# displaycontrol.net
KiCad netlist of a schematic drawn in EAGLE
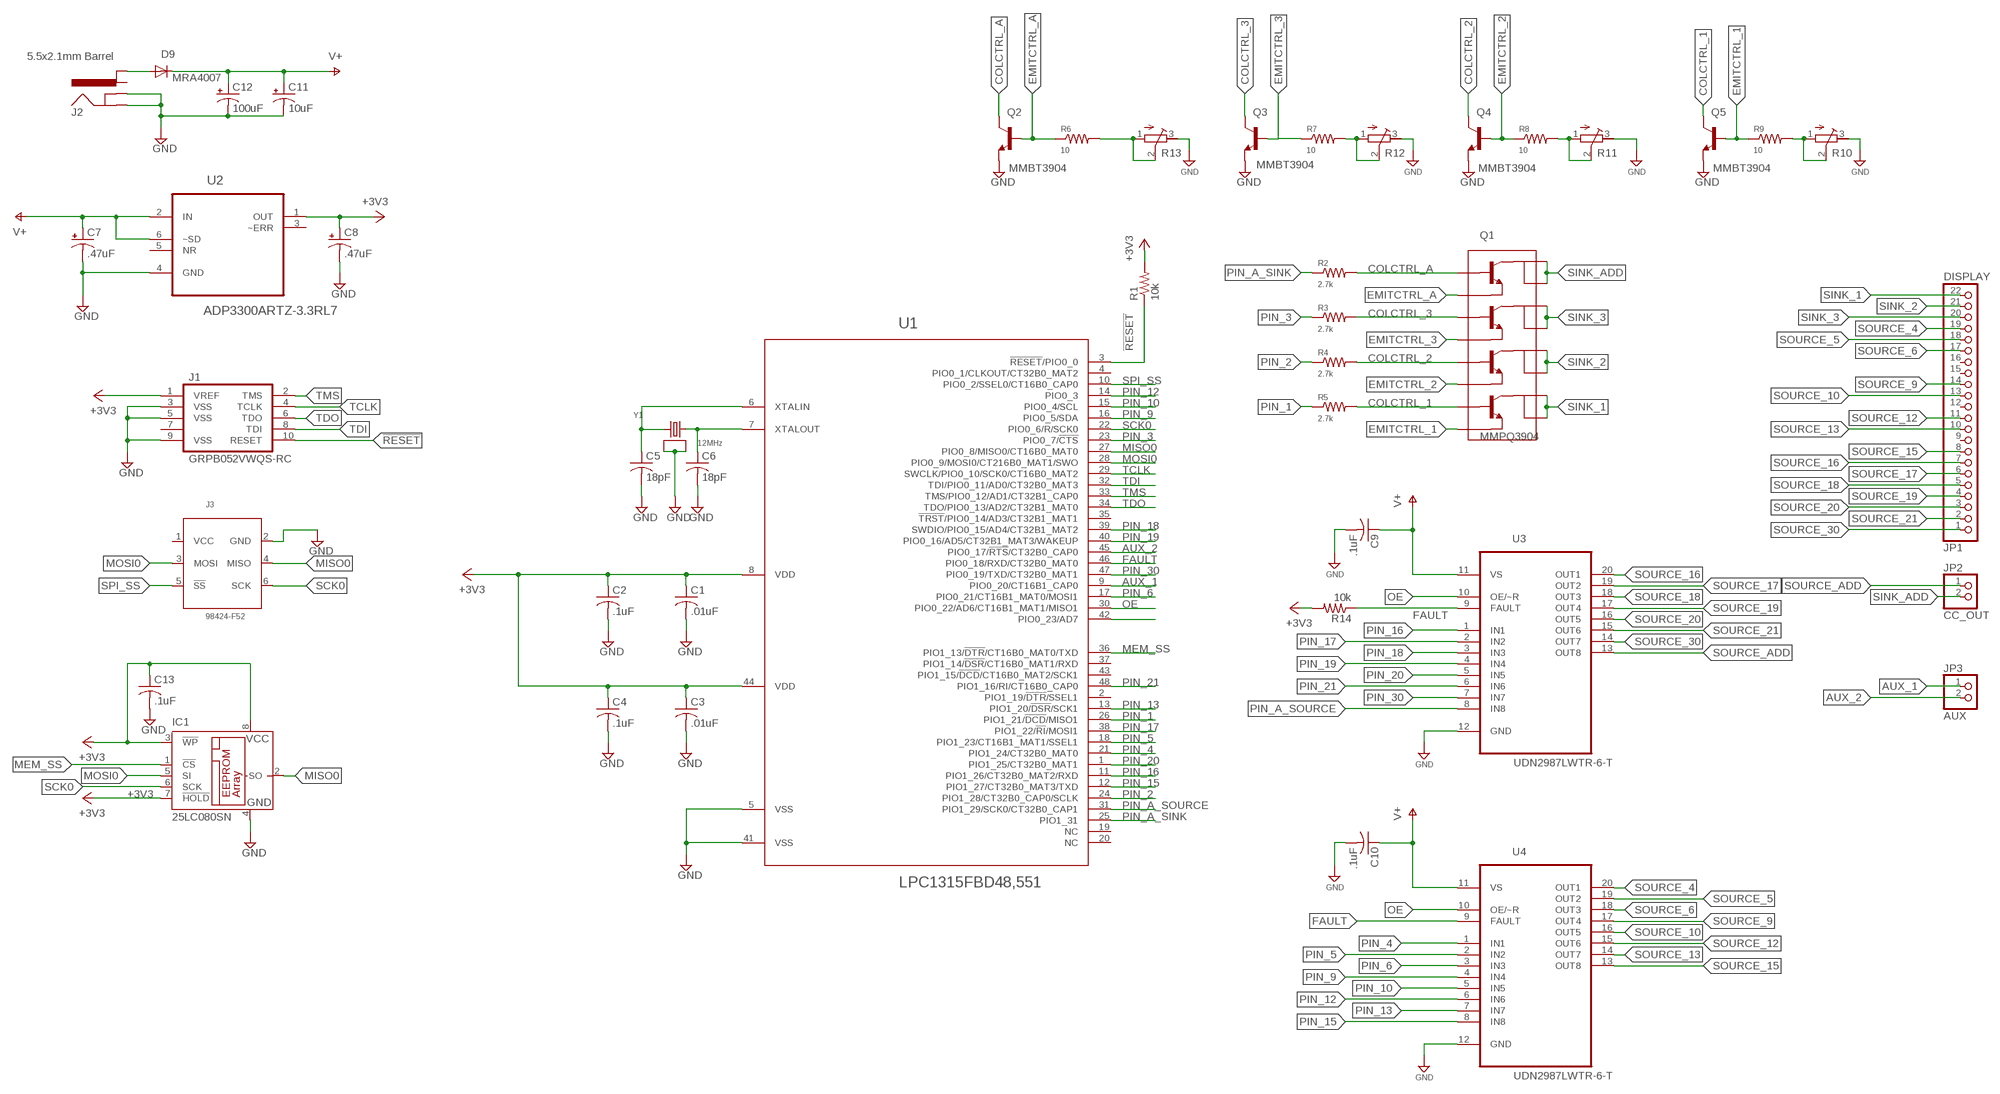
[diagram p0: schematic, sheet 1]

(export (version "E")
  (design (tool "Eeschema 10.0.6"))
  (components
    (comp (ref "C1")
      (value ".01uF")
      (footprint "eagle-import:C0805")
      (libsource (lib "eagle-import") (part "C-USC0805"))
    )
    (comp (ref "C2")
      (value ".1uF")
      (footprint "eagle-import:C0805")
      (libsource (lib "eagle-import") (part "C-USC0805"))
    )
    (comp (ref "C3")
      (value ".01uF")
      (footprint "eagle-import:C0805")
      (libsource (lib "eagle-import") (part "C-USC0805"))
    )
    (comp (ref "C4")
      (value ".1uF")
      (footprint "eagle-import:C0805")
      (libsource (lib "eagle-import") (part "C-USC0805"))
    )
    (comp (ref "C5")
      (value "18pF")
      (footprint "eagle-import:C0805")
      (libsource (lib "eagle-import") (part "C-USC0805"))
    )
    (comp (ref "C6")
      (value "18pF")
      (footprint "eagle-import:C0805")
      (libsource (lib "eagle-import") (part "C-USC0805"))
    )
    (comp (ref "C7")
      (value ".47uF")
      (footprint "eagle-import:EIA3216")
      (libsource (lib "eagle-import") (part "CAP_POL1206"))
    )
    (comp (ref "C8")
      (value ".47uF")
      (footprint "eagle-import:EIA3216")
      (libsource (lib "eagle-import") (part "CAP_POL1206"))
    )
    (comp (ref "C9")
      (value ".1uF")
      (footprint "eagle-import:C0805")
      (libsource (lib "eagle-import") (part "C-USC0805"))
    )
    (comp (ref "C10")
      (value ".1uF")
      (footprint "eagle-import:C0805")
      (libsource (lib "eagle-import") (part "C-USC0805"))
    )
    (comp (ref "C11")
      (value "10uF")
      (footprint "eagle-import:153CLV-0405")
      (libsource (lib "eagle-import") (part "CPOL-US153CLV-0405"))
    )
    (comp (ref "C12")
      (value "100uF")
      (footprint "eagle-import:153CLV-0605")
      (libsource (lib "eagle-import") (part "CPOL-US153CLV-0605"))
    )
    (comp (ref "C13")
      (value ".1uF")
      (footprint "eagle-import:C0805")
      (libsource (lib "eagle-import") (part "C-USC0805"))
    )
    (comp (ref "D9")
      (value "MRA4007")
      (footprint "eagle-import:SOD-123_MINI-SMA")
      (libsource (lib "eagle-import") (part "CGRM400-G7"))
    )
    (comp (ref "IC1")
      (value "25LC080SN")
      (footprint "eagle-import:SO-08")
      (fields (field (name "MF") "MICROCHIP") (field (name "MPN") "25LC080/SN"))
      (libsource (lib "eagle-import") (part "25SNLC080"))
    )
    (comp (ref "J1")
      (value "GRPB052VWQS-RC")
      (footprint "eagle-import:GRPB052VWQS-RC")
      (libsource (lib "eagle-import") (part "GRPB052VWQS-RC"))
    )
    (comp (ref "J2")
      (value "5.5x2.1mm Barrel")
      (footprint "eagle-import:POWER_JACK_SMD")
      (libsource (lib "eagle-import") (part "POWER_JACKSMD"))
    )
    (comp (ref "J3")
      (value "98424-F52")
      (footprint "eagle-import:2X3_2MM_SMD")
      (libsource (lib "eagle-import") (part "98424-F52"))
    )
    (comp (ref "JP1")
      (value "DISPLAY")
      (footprint "eagle-import:1X22")
      (libsource (lib "eagle-import") (part "PINHD-1X22"))
    )
    (comp (ref "JP2")
      (value "CC_OUT")
      (footprint "eagle-import:1X02")
      (libsource (lib "eagle-import") (part "PINHD-1X2"))
    )
    (comp (ref "JP3")
      (value "AUX")
      (footprint "eagle-import:1X02")
      (libsource (lib "eagle-import") (part "PINHD-1X2"))
    )
    (comp (ref "Q1")
      (value "MMPQ3904")
      (footprint "eagle-import:SO16")
      (libsource (lib "eagle-import") (part "MMPQ3904"))
    )
    (comp (ref "Q2")
      (value "MMBT3904")
      (footprint "eagle-import:SOT23-3")
      (libsource (lib "eagle-import") (part "TRANSISTOR_NPNMMBT2222A"))
    )
    (comp (ref "Q3")
      (value "MMBT3904")
      (footprint "eagle-import:SOT23-3")
      (libsource (lib "eagle-import") (part "TRANSISTOR_NPNMMBT2222A"))
    )
    (comp (ref "Q4")
      (value "MMBT3904")
      (footprint "eagle-import:SOT23-3")
      (libsource (lib "eagle-import") (part "TRANSISTOR_NPNMMBT2222A"))
    )
    (comp (ref "Q5")
      (value "MMBT3904")
      (footprint "eagle-import:SOT23-3")
      (libsource (lib "eagle-import") (part "TRANSISTOR_NPNMMBT2222A"))
    )
    (comp (ref "R1")
      (value "10k")
      (footprint "eagle-import:R0805")
      (libsource (lib "eagle-import") (part "R-US_R0805"))
    )
    (comp (ref "R2")
      (value "2.7k")
      (footprint "eagle-import:R0805")
      (libsource (lib "eagle-import") (part "R-US_R0805"))
    )
    (comp (ref "R3")
      (value "2.7k")
      (footprint "eagle-import:R0805")
      (libsource (lib "eagle-import") (part "R-US_R0805"))
    )
    (comp (ref "R4")
      (value "2.7k")
      (footprint "eagle-import:R0805")
      (libsource (lib "eagle-import") (part "R-US_R0805"))
    )
    (comp (ref "R5")
      (value "2.7k")
      (footprint "eagle-import:R0805")
      (libsource (lib "eagle-import") (part "R-US_R0805"))
    )
    (comp (ref "R6")
      (value "10")
      (footprint "eagle-import:R0805")
      (libsource (lib "eagle-import") (part "R-US_R0805"))
    )
    (comp (ref "R7")
      (value "10")
      (footprint "eagle-import:R0805")
      (libsource (lib "eagle-import") (part "R-US_R0805"))
    )
    (comp (ref "R8")
      (value "10")
      (footprint "eagle-import:R0805")
      (libsource (lib "eagle-import") (part "R-US_R0805"))
    )
    (comp (ref "R9")
      (value "10")
      (footprint "eagle-import:R0805")
      (libsource (lib "eagle-import") (part "R-US_R0805"))
    )
    (comp (ref "R10")
      (value "R-TRIMM3214W")
      (footprint "eagle-import:RTRIM3214W")
      (libsource (lib "eagle-import") (part "R-TRIMM3214W"))
    )
    (comp (ref "R11")
      (value "R-TRIMM3214W")
      (footprint "eagle-import:RTRIM3214W")
      (libsource (lib "eagle-import") (part "R-TRIMM3214W"))
    )
    (comp (ref "R12")
      (value "R-TRIMM3214W")
      (footprint "eagle-import:RTRIM3214W")
      (libsource (lib "eagle-import") (part "R-TRIMM3214W"))
    )
    (comp (ref "R13")
      (value "R-TRIMM3214W")
      (footprint "eagle-import:RTRIM3214W")
      (libsource (lib "eagle-import") (part "R-TRIMM3214W"))
    )
    (comp (ref "R14")
      (value "10k")
      (footprint "eagle-import:R0805")
      (libsource (lib "eagle-import") (part "R-US_R0805"))
    )
    (comp (ref "U1")
      (value "LPC1315FBD48,551")
      (footprint "eagle-import:QFP50P900X900X160-48N")
      (libsource (lib "eagle-import") (part "LPC1315FBD48,551"))
    )
    (comp (ref "U2")
      (value "ADP3300ARTZ-3.3RL7")
      (footprint "eagle-import:SOT95P275X145-6N")
      (libsource (lib "eagle-import") (part "ADP3300ARTZ-3.3RL7"))
    )
    (comp (ref "U3")
      (value "UDN2987LWTR-6-T")
      (footprint "eagle-import:SO20W")
      (libsource (lib "eagle-import") (part "UDN2987LWTR-6-T"))
    )
    (comp (ref "U4")
      (value "UDN2987LWTR-6-T")
      (footprint "eagle-import:SO20W")
      (libsource (lib "eagle-import") (part "UDN2987LWTR-6-T"))
    )
    (comp (ref "Y1")
      (value "12MHz")
      (footprint "eagle-import:5X3.2MM")
      (libsource (lib "eagle-import") (part "CRYSTAL.5X3.2MM"))
    )
  )
  (nets
    (net (code "1") (name "+3V3") (class "Default")
      (node (ref "C1") (pin "1") (pinfunction "1_1") (pintype "passive"))
      (node (ref "C13") (pin "1") (pinfunction "1_1") (pintype "passive"))
      (node (ref "C2") (pin "1") (pinfunction "1_1") (pintype "passive"))
      (node (ref "C3") (pin "1") (pinfunction "1_1") (pintype "passive"))
      (node (ref "C4") (pin "1") (pinfunction "1_1") (pintype "passive"))
      (node (ref "C8") (pin "A") (pinfunction "+_A") (pintype "passive"))
      (node (ref "IC1") (pin "3") (pinfunction "~{WP}_3") (pintype "input"))
      (node (ref "IC1") (pin "7") (pinfunction "~{HOLD}_7") (pintype "input"))
      (node (ref "IC1") (pin "8") (pinfunction "VCC_8") (pintype "power_in"))
      (node (ref "J1") (pin "1") (pinfunction "VREF_1") (pintype "power_in"))
      (node (ref "R1") (pin "2") (pinfunction "2_2") (pintype "passive"))
      (node (ref "R14") (pin "2") (pinfunction "2_2") (pintype "passive"))
      (node (ref "U1") (pin "44") (pinfunction "VDD_44") (pintype "power_in"))
      (node (ref "U1") (pin "8") (pinfunction "VDD_8") (pintype "power_in"))
      (node (ref "U2") (pin "1") (pinfunction "OUT_1") (pintype "output"))
    )
    (net (code "2") (name "/VCC") (class "Default")
      (node (ref "J3") (pin "1") (pinfunction "VCC_1") (pintype "power_in"))
    )
    (net (code "3") (name "/~{RESET}") (class "Default")
      (node (ref "J1") (pin "10") (pinfunction "RESET_10") (pintype "bidirectional"))
      (node (ref "R1") (pin "1") (pinfunction "1_1") (pintype "passive"))
      (node (ref "U1") (pin "3") (pinfunction "~{RESET}/PIO0_0_3") (pintype "bidirectional"))
    )
    (net (code "4") (name "AUX_1") (class "Default")
      (node (ref "JP3") (pin "1") (pinfunction "1_1") (pintype "passive"))
      (node (ref "U1") (pin "9") (pinfunction "PIO0_20/CT16B1_CAP0_9") (pintype "bidirectional"))
    )
    (net (code "5") (name "AUX_2") (class "Default")
      (node (ref "JP3") (pin "2") (pinfunction "2_2") (pintype "passive"))
      (node (ref "U1") (pin "45") (pinfunction "PIO0_17/~{RTS}/CT32B0_CAP0_45") (pintype "bidirectional"))
    )
    (net (code "6") (name "COLCTRL_1") (class "Default")
      (node (ref "Q1") (pin "9") (pinfunction "B4_9") (pintype "passive"))
      (node (ref "Q5") (pin "3") (pinfunction "C_3") (pintype "passive"))
      (node (ref "R5") (pin "2") (pinfunction "2_2") (pintype "passive"))
    )
    (net (code "7") (name "COLCTRL_2") (class "Default")
      (node (ref "Q1") (pin "11") (pinfunction "B3_11") (pintype "passive"))
      (node (ref "Q4") (pin "3") (pinfunction "C_3") (pintype "passive"))
      (node (ref "R4") (pin "2") (pinfunction "2_2") (pintype "passive"))
    )
    (net (code "8") (name "COLCTRL_3") (class "Default")
      (node (ref "Q1") (pin "13") (pinfunction "B2_13") (pintype "passive"))
      (node (ref "Q3") (pin "3") (pinfunction "C_3") (pintype "passive"))
      (node (ref "R3") (pin "2") (pinfunction "2_2") (pintype "passive"))
    )
    (net (code "9") (name "COLCTRL_A") (class "Default")
      (node (ref "Q1") (pin "15") (pinfunction "B1_15") (pintype "passive"))
      (node (ref "Q2") (pin "3") (pinfunction "C_3") (pintype "passive"))
      (node (ref "R2") (pin "2") (pinfunction "2_2") (pintype "passive"))
    )
    (net (code "10") (name "EMITCTRL_1") (class "Default")
      (node (ref "Q1") (pin "10") (pinfunction "E4_10") (pintype "passive"))
      (node (ref "Q5") (pin "1") (pinfunction "B_1") (pintype "passive"))
      (node (ref "R9") (pin "1") (pinfunction "1_1") (pintype "passive"))
    )
    (net (code "11") (name "EMITCTRL_2") (class "Default")
      (node (ref "Q1") (pin "12") (pinfunction "E3_12") (pintype "passive"))
      (node (ref "Q4") (pin "1") (pinfunction "B_1") (pintype "passive"))
      (node (ref "R8") (pin "1") (pinfunction "1_1") (pintype "passive"))
    )
    (net (code "12") (name "EMITCTRL_3") (class "Default")
      (node (ref "Q1") (pin "14") (pinfunction "E2_14") (pintype "passive"))
      (node (ref "Q3") (pin "1") (pinfunction "B_1") (pintype "passive"))
      (node (ref "R7") (pin "1") (pinfunction "1_1") (pintype "passive"))
    )
    (net (code "13") (name "EMITCTRL_A") (class "Default")
      (node (ref "Q1") (pin "16") (pinfunction "E1_16") (pintype "passive"))
      (node (ref "Q2") (pin "1") (pinfunction "B_1") (pintype "passive"))
      (node (ref "R6") (pin "1") (pinfunction "1_1") (pintype "passive"))
    )
    (net (code "14") (name "FAULT") (class "Default")
      (node (ref "R14") (pin "1") (pinfunction "1_1") (pintype "passive"))
      (node (ref "U1") (pin "46") (pinfunction "PIO0_18/RXD/CT32B0_MAT0_46") (pintype "bidirectional"))
      (node (ref "U3") (pin "9") (pinfunction "FAULT_9") (pintype "input"))
      (node (ref "U4") (pin "9") (pinfunction "FAULT_9") (pintype "input"))
    )
    (net (code "15") (name "GND") (class "Default")
      (node (ref "C1") (pin "2") (pinfunction "2_2") (pintype "passive"))
      (node (ref "C10") (pin "2") (pinfunction "2_2") (pintype "passive"))
      (node (ref "C11") (pin "-") (pinfunction "-_-") (pintype "passive"))
      (node (ref "C12") (pin "-") (pinfunction "-_-") (pintype "passive"))
      (node (ref "C13") (pin "2") (pinfunction "2_2") (pintype "passive"))
      (node (ref "C2") (pin "2") (pinfunction "2_2") (pintype "passive"))
      (node (ref "C3") (pin "2") (pinfunction "2_2") (pintype "passive"))
      (node (ref "C4") (pin "2") (pinfunction "2_2") (pintype "passive"))
      (node (ref "C5") (pin "2") (pinfunction "2_2") (pintype "passive"))
      (node (ref "C6") (pin "2") (pinfunction "2_2") (pintype "passive"))
      (node (ref "C7") (pin "C") (pinfunction "-_C") (pintype "passive"))
      (node (ref "C8") (pin "C") (pinfunction "-_C") (pintype "passive"))
      (node (ref "C9") (pin "2") (pinfunction "2_2") (pintype "passive"))
      (node (ref "IC1") (pin "4") (pinfunction "GND_4") (pintype "power_in"))
      (node (ref "J1") (pin "3") (pinfunction "VSS_3") (pintype "passive"))
      (node (ref "J1") (pin "5") (pinfunction "VSS_5") (pintype "passive"))
      (node (ref "J1") (pin "9") (pinfunction "VSS_9") (pintype "passive"))
      (node (ref "J2") (pin "GND") (pinfunction "GNDBREAK_GND") (pintype "bidirectional"))
      (node (ref "J2") (pin "P$4") (pinfunction "GND_P$4") (pintype "bidirectional"))
      (node (ref "J3") (pin "2") (pinfunction "GND_2") (pintype "passive"))
      (node (ref "Q2") (pin "2") (pinfunction "E_2") (pintype "passive"))
      (node (ref "Q3") (pin "2") (pinfunction "E_2") (pintype "passive"))
      (node (ref "Q4") (pin "2") (pinfunction "E_2") (pintype "passive"))
      (node (ref "Q5") (pin "2") (pinfunction "E_2") (pintype "passive"))
      (node (ref "R10") (pin "3") (pinfunction "A_3") (pintype "passive"))
      (node (ref "R11") (pin "3") (pinfunction "A_3") (pintype "passive"))
      (node (ref "R12") (pin "3") (pinfunction "A_3") (pintype "passive"))
      (node (ref "R13") (pin "3") (pinfunction "A_3") (pintype "passive"))
      (node (ref "U1") (pin "41") (pinfunction "VSS_41") (pintype "passive"))
      (node (ref "U1") (pin "5") (pinfunction "VSS_5") (pintype "passive"))
      (node (ref "U2") (pin "4") (pinfunction "GND_4") (pintype "passive"))
      (node (ref "U3") (pin "12") (pinfunction "GND_12") (pintype "passive"))
      (node (ref "U4") (pin "12") (pinfunction "GND_12") (pintype "passive"))
      (node (ref "Y1") (pin "2") (pinfunction "GND_2") (pintype "passive"))
      (node (ref "Y1") (pin "4") (pinfunction "GND_4") (pintype "passive"))
    )
    (net (code "16") (name "MEM_SS") (class "Default")
      (node (ref "IC1") (pin "1") (pinfunction "~{CS}_1") (pintype "input"))
      (node (ref "U1") (pin "36") (pinfunction "PIO1_13/~{DTR}/CT16B0_MAT0/TXD_36") (pintype "bidirectional"))
    )
    (net (code "17") (name "MISO0") (class "Default")
      (node (ref "IC1") (pin "2") (pinfunction "SO_2") (pintype "bidirectional"))
      (node (ref "J3") (pin "4") (pinfunction "MISO_4") (pintype "bidirectional"))
      (node (ref "U1") (pin "27") (pinfunction "PIO0_8/MISO0/CT16B0_MAT0_27") (pintype "bidirectional"))
    )
    (net (code "18") (name "MOSI0") (class "Default")
      (node (ref "IC1") (pin "5") (pinfunction "SI_5") (pintype "input"))
      (node (ref "J3") (pin "3") (pinfunction "MOSI_3") (pintype "bidirectional"))
      (node (ref "U1") (pin "28") (pinfunction "PIO0_9/MOSI0/CT216B0_MAT1/SWO_28") (pintype "bidirectional"))
    )
    (net (code "19") (name "Net-(J2-PWR1)") (class "Default")
      (node (ref "D9") (pin "A") (pinfunction "A_A") (pintype "passive"))
      (node (ref "J2") (pin "VIN1") (pinfunction "PWR1_VIN1") (pintype "bidirectional"))
    )
    (net (code "20") (name "Net-(R10-E)") (class "Default")
      (node (ref "R10") (pin "1") (pinfunction "E_1") (pintype "passive"))
      (node (ref "R10") (pin "2") (pinfunction "S_2") (pintype "passive"))
      (node (ref "R9") (pin "2") (pinfunction "2_2") (pintype "passive"))
    )
    (net (code "21") (name "Net-(R11-E)") (class "Default")
      (node (ref "R11") (pin "1") (pinfunction "E_1") (pintype "passive"))
      (node (ref "R11") (pin "2") (pinfunction "S_2") (pintype "passive"))
      (node (ref "R8") (pin "2") (pinfunction "2_2") (pintype "passive"))
    )
    (net (code "22") (name "Net-(R12-E)") (class "Default")
      (node (ref "R12") (pin "1") (pinfunction "E_1") (pintype "passive"))
      (node (ref "R12") (pin "2") (pinfunction "S_2") (pintype "passive"))
      (node (ref "R7") (pin "2") (pinfunction "2_2") (pintype "passive"))
    )
    (net (code "23") (name "Net-(R13-E)") (class "Default")
      (node (ref "R13") (pin "1") (pinfunction "E_1") (pintype "passive"))
      (node (ref "R13") (pin "2") (pinfunction "S_2") (pintype "passive"))
      (node (ref "R6") (pin "2") (pinfunction "2_2") (pintype "passive"))
    )
    (net (code "24") (name "Net-(U1-XTALIN)") (class "Default")
      (node (ref "C5") (pin "1") (pinfunction "1_1") (pintype "passive"))
      (node (ref "U1") (pin "6") (pinfunction "XTALIN_6") (pintype "input"))
      (node (ref "Y1") (pin "1") (pinfunction "1_1") (pintype "passive"))
    )
    (net (code "25") (name "Net-(U1-XTALOUT)") (class "Default")
      (node (ref "C6") (pin "1") (pinfunction "1_1") (pintype "passive"))
      (node (ref "U1") (pin "7") (pinfunction "XTALOUT_7") (pintype "bidirectional"))
      (node (ref "Y1") (pin "3") (pinfunction "2_3") (pintype "passive"))
    )
    (net (code "26") (name "OE") (class "Default")
      (node (ref "U1") (pin "30") (pinfunction "PIO0_22/AD6/CT16B1_MAT1/MISO1_30") (pintype "bidirectional"))
      (node (ref "U3") (pin "10") (pinfunction "OE/~{R}_10") (pintype "input"))
      (node (ref "U4") (pin "10") (pinfunction "OE/~{R}_10") (pintype "input"))
    )
    (net (code "27") (name "PIN_1") (class "Default")
      (node (ref "R5") (pin "1") (pinfunction "1_1") (pintype "passive"))
      (node (ref "U1") (pin "26") (pinfunction "PIO1_21/~{DCD}/MISO1_26") (pintype "bidirectional"))
    )
    (net (code "28") (name "PIN_2") (class "Default")
      (node (ref "R4") (pin "1") (pinfunction "1_1") (pintype "passive"))
      (node (ref "U1") (pin "24") (pinfunction "PIO1_28/CT32B0_CAP0/SCLK_24") (pintype "bidirectional"))
    )
    (net (code "29") (name "PIN_3") (class "Default")
      (node (ref "R3") (pin "1") (pinfunction "1_1") (pintype "passive"))
      (node (ref "U1") (pin "23") (pinfunction "PIO0_7/~{CTS}_23") (pintype "bidirectional"))
    )
    (net (code "30") (name "PIN_4") (class "Default")
      (node (ref "U1") (pin "21") (pinfunction "PIO1_24/CT32B0_MAT0_21") (pintype "bidirectional"))
      (node (ref "U4") (pin "1") (pinfunction "IN1_1") (pintype "input"))
    )
    (net (code "31") (name "PIN_5") (class "Default")
      (node (ref "U1") (pin "18") (pinfunction "PIO1_23/CT16B1_MAT1/SSEL1_18") (pintype "bidirectional"))
      (node (ref "U4") (pin "2") (pinfunction "IN2_2") (pintype "input"))
    )
    (net (code "32") (name "PIN_6") (class "Default")
      (node (ref "U1") (pin "17") (pinfunction "PIO0_21/CT16B1_MAT0/MOSI1_17") (pintype "bidirectional"))
      (node (ref "U4") (pin "3") (pinfunction "IN3_3") (pintype "input"))
    )
    (net (code "33") (name "PIN_9") (class "Default")
      (node (ref "U1") (pin "16") (pinfunction "PIO0_5/SDA_16") (pintype "bidirectional"))
      (node (ref "U4") (pin "4") (pinfunction "IN4_4") (pintype "input"))
    )
    (net (code "34") (name "PIN_10") (class "Default")
      (node (ref "U1") (pin "15") (pinfunction "PIO0_4/SCL_15") (pintype "bidirectional"))
      (node (ref "U4") (pin "5") (pinfunction "IN5_5") (pintype "input"))
    )
    (net (code "35") (name "PIN_12") (class "Default")
      (node (ref "U1") (pin "14") (pinfunction "PIO0_3_14") (pintype "bidirectional"))
      (node (ref "U4") (pin "6") (pinfunction "IN6_6") (pintype "input"))
    )
    (net (code "36") (name "PIN_13") (class "Default")
      (node (ref "U1") (pin "13") (pinfunction "PIO1_20/~{DSR}/SCK1_13") (pintype "bidirectional"))
      (node (ref "U4") (pin "7") (pinfunction "IN7_7") (pintype "input"))
    )
    (net (code "37") (name "PIN_15") (class "Default")
      (node (ref "U1") (pin "12") (pinfunction "PIO1_27/CT32B0_MAT3/TXD_12") (pintype "bidirectional"))
      (node (ref "U4") (pin "8") (pinfunction "IN8_8") (pintype "input"))
    )
    (net (code "38") (name "PIN_16") (class "Default")
      (node (ref "U1") (pin "11") (pinfunction "PIO1_26/CT32B0_MAT2/RXD_11") (pintype "bidirectional"))
      (node (ref "U3") (pin "1") (pinfunction "IN1_1") (pintype "input"))
    )
    (net (code "39") (name "PIN_17") (class "Default")
      (node (ref "U1") (pin "38") (pinfunction "PIO1_22/~{RI}/MOSI1_38") (pintype "bidirectional"))
      (node (ref "U3") (pin "2") (pinfunction "IN2_2") (pintype "input"))
    )
    (net (code "40") (name "PIN_18") (class "Default")
      (node (ref "U1") (pin "39") (pinfunction "SWDIO/PIO0_15/AD4/CT32B1_MAT2_39") (pintype "bidirectional"))
      (node (ref "U3") (pin "3") (pinfunction "IN3_3") (pintype "input"))
    )
    (net (code "41") (name "PIN_19") (class "Default")
      (node (ref "U1") (pin "40") (pinfunction "PIO0_16/AD5/CT32B1_MAT3/WAKEUP_40") (pintype "bidirectional"))
      (node (ref "U3") (pin "4") (pinfunction "IN4_4") (pintype "input"))
    )
    (net (code "42") (name "PIN_20") (class "Default")
      (node (ref "U1") (pin "1") (pinfunction "PIO1_25/CT32B0_MAT1_1") (pintype "bidirectional"))
      (node (ref "U3") (pin "5") (pinfunction "IN5_5") (pintype "input"))
    )
    (net (code "43") (name "PIN_21") (class "Default")
      (node (ref "U1") (pin "48") (pinfunction "PIO1_16/RI/CT16B0_CAP0_48") (pintype "bidirectional"))
      (node (ref "U3") (pin "6") (pinfunction "IN6_6") (pintype "input"))
    )
    (net (code "44") (name "PIN_30") (class "Default")
      (node (ref "U1") (pin "47") (pinfunction "PIO0_19/TXD/CT32B0_MAT1_47") (pintype "bidirectional"))
      (node (ref "U3") (pin "7") (pinfunction "IN7_7") (pintype "input"))
    )
    (net (code "45") (name "PIN_A_SINK") (class "Default")
      (node (ref "R2") (pin "1") (pinfunction "1_1") (pintype "passive"))
      (node (ref "U1") (pin "25") (pinfunction "PIO1_31_25") (pintype "bidirectional"))
    )
    (net (code "46") (name "PIN_A_SOURCE") (class "Default")
      (node (ref "U1") (pin "31") (pinfunction "PIO1_29/SCK0/CT32B0_CAP1_31") (pintype "bidirectional"))
      (node (ref "U3") (pin "8") (pinfunction "IN8_8") (pintype "input"))
    )
    (net (code "47") (name "SCK0") (class "Default")
      (node (ref "IC1") (pin "6") (pinfunction "SCK_6") (pintype "input"))
      (node (ref "J3") (pin "6") (pinfunction "SCK_6") (pintype "bidirectional"))
      (node (ref "U1") (pin "22") (pinfunction "PIO0_6/R/SCK0_22") (pintype "bidirectional"))
    )
    (net (code "48") (name "SINK_1") (class "Default")
      (node (ref "JP1") (pin "22") (pinfunction "22_22") (pintype "passive"))
      (node (ref "Q1") (pin "7") (pinfunction "C4_7") (pintype "passive"))
      (node (ref "Q1") (pin "8") (pinfunction "C4_8") (pintype "passive"))
    )
    (net (code "49") (name "SINK_2") (class "Default")
      (node (ref "JP1") (pin "21") (pinfunction "21_21") (pintype "passive"))
      (node (ref "Q1") (pin "5") (pinfunction "C3_5") (pintype "passive"))
      (node (ref "Q1") (pin "6") (pinfunction "C3_6") (pintype "passive"))
    )
    (net (code "50") (name "SINK_3") (class "Default")
      (node (ref "JP1") (pin "20") (pinfunction "20_20") (pintype "passive"))
      (node (ref "Q1") (pin "3") (pinfunction "C2_3") (pintype "passive"))
      (node (ref "Q1") (pin "4") (pinfunction "C2_4") (pintype "passive"))
    )
    (net (code "51") (name "SINK_ADD") (class "Default")
      (node (ref "JP2") (pin "2") (pinfunction "2_2") (pintype "passive"))
      (node (ref "Q1") (pin "1") (pinfunction "C1_1") (pintype "passive"))
      (node (ref "Q1") (pin "2") (pinfunction "C1_2") (pintype "passive"))
    )
    (net (code "52") (name "SOURCE_4") (class "Default")
      (node (ref "JP1") (pin "19") (pinfunction "19_19") (pintype "passive"))
      (node (ref "U4") (pin "20") (pinfunction "OUT1_20") (pintype "output"))
    )
    (net (code "53") (name "SOURCE_5") (class "Default")
      (node (ref "JP1") (pin "18") (pinfunction "18_18") (pintype "passive"))
      (node (ref "U4") (pin "19") (pinfunction "OUT2_19") (pintype "output"))
    )
    (net (code "54") (name "SOURCE_6") (class "Default")
      (node (ref "JP1") (pin "17") (pinfunction "17_17") (pintype "passive"))
      (node (ref "U4") (pin "18") (pinfunction "OUT3_18") (pintype "output"))
    )
    (net (code "55") (name "SOURCE_9") (class "Default")
      (node (ref "JP1") (pin "14") (pinfunction "14_14") (pintype "passive"))
      (node (ref "U4") (pin "17") (pinfunction "OUT4_17") (pintype "output"))
    )
    (net (code "56") (name "SOURCE_10") (class "Default")
      (node (ref "JP1") (pin "13") (pinfunction "13_13") (pintype "passive"))
      (node (ref "U4") (pin "16") (pinfunction "OUT5_16") (pintype "output"))
    )
    (net (code "57") (name "SOURCE_12") (class "Default")
      (node (ref "JP1") (pin "11") (pinfunction "11_11") (pintype "passive"))
      (node (ref "U4") (pin "15") (pinfunction "OUT6_15") (pintype "output"))
    )
    (net (code "58") (name "SOURCE_13") (class "Default")
      (node (ref "JP1") (pin "10") (pinfunction "10_10") (pintype "passive"))
      (node (ref "U4") (pin "14") (pinfunction "OUT7_14") (pintype "output"))
    )
    (net (code "59") (name "SOURCE_15") (class "Default")
      (node (ref "JP1") (pin "8") (pinfunction "8_8") (pintype "passive"))
      (node (ref "U4") (pin "13") (pinfunction "OUT8_13") (pintype "output"))
    )
    (net (code "60") (name "SOURCE_16") (class "Default")
      (node (ref "JP1") (pin "7") (pinfunction "7_7") (pintype "passive"))
      (node (ref "U3") (pin "20") (pinfunction "OUT1_20") (pintype "output"))
    )
    (net (code "61") (name "SOURCE_17") (class "Default")
      (node (ref "JP1") (pin "6") (pinfunction "6_6") (pintype "passive"))
      (node (ref "U3") (pin "19") (pinfunction "OUT2_19") (pintype "output"))
    )
    (net (code "62") (name "SOURCE_18") (class "Default")
      (node (ref "JP1") (pin "5") (pinfunction "5_5") (pintype "passive"))
      (node (ref "U3") (pin "18") (pinfunction "OUT3_18") (pintype "output"))
    )
    (net (code "63") (name "SOURCE_19") (class "Default")
      (node (ref "JP1") (pin "4") (pinfunction "4_4") (pintype "passive"))
      (node (ref "U3") (pin "17") (pinfunction "OUT4_17") (pintype "output"))
    )
    (net (code "64") (name "SOURCE_20") (class "Default")
      (node (ref "JP1") (pin "3") (pinfunction "3_3") (pintype "passive"))
      (node (ref "U3") (pin "16") (pinfunction "OUT5_16") (pintype "output"))
    )
    (net (code "65") (name "SOURCE_21") (class "Default")
      (node (ref "JP1") (pin "2") (pinfunction "2_2") (pintype "passive"))
      (node (ref "U3") (pin "15") (pinfunction "OUT6_15") (pintype "output"))
    )
    (net (code "66") (name "SOURCE_30") (class "Default")
      (node (ref "JP1") (pin "1") (pinfunction "1_1") (pintype "passive"))
      (node (ref "U3") (pin "14") (pinfunction "OUT7_14") (pintype "output"))
    )
    (net (code "67") (name "SOURCE_ADD") (class "Default")
      (node (ref "JP2") (pin "1") (pinfunction "1_1") (pintype "passive"))
      (node (ref "U3") (pin "13") (pinfunction "OUT8_13") (pintype "output"))
    )
    (net (code "68") (name "SPI_SS") (class "Default")
      (node (ref "J3") (pin "5") (pinfunction "~{SS}_5") (pintype "bidirectional"))
      (node (ref "U1") (pin "10") (pinfunction "PIO0_2/SSEL0/CT16B0_CAP0_10") (pintype "bidirectional"))
    )
    (net (code "69") (name "TCLK") (class "Default")
      (node (ref "J1") (pin "4") (pinfunction "TCLK_4") (pintype "bidirectional"))
      (node (ref "U1") (pin "29") (pinfunction "SWCLK/PIO0_10/SCK0/CT16B0_MAT2_29") (pintype "bidirectional"))
    )
    (net (code "70") (name "TDI") (class "Default")
      (node (ref "J1") (pin "8") (pinfunction "TDI_8") (pintype "bidirectional"))
      (node (ref "U1") (pin "32") (pinfunction "TDI/PIO0_11/AD0/CT32B0_MAT3_32") (pintype "bidirectional"))
    )
    (net (code "71") (name "TDO") (class "Default")
      (node (ref "J1") (pin "6") (pinfunction "TDO_6") (pintype "bidirectional"))
      (node (ref "U1") (pin "34") (pinfunction "TDO/PIO0_13/AD2/CT32B1_MAT0_34") (pintype "bidirectional"))
    )
    (net (code "72") (name "TMS") (class "Default")
      (node (ref "J1") (pin "2") (pinfunction "TMS_2") (pintype "bidirectional"))
      (node (ref "U1") (pin "33") (pinfunction "TMS/PIO0_12/AD1/CT32B1_CAP0_33") (pintype "bidirectional"))
    )
    (net (code "73") (name "V+") (class "Default")
      (node (ref "C10") (pin "1") (pinfunction "1_1") (pintype "passive"))
      (node (ref "C11") (pin "+") (pinfunction "+_+") (pintype "passive"))
      (node (ref "C12") (pin "+") (pinfunction "+_+") (pintype "passive"))
      (node (ref "C7") (pin "A") (pinfunction "+_A") (pintype "passive"))
      (node (ref "C9") (pin "1") (pinfunction "1_1") (pintype "passive"))
      (node (ref "D9") (pin "C") (pinfunction "C_C") (pintype "passive"))
      (node (ref "U2") (pin "2") (pinfunction "IN_2") (pintype "power_in"))
      (node (ref "U2") (pin "6") (pinfunction "~{SD}_6") (pintype "input"))
      (node (ref "U3") (pin "11") (pinfunction "VS_11") (pintype "power_in"))
      (node (ref "U4") (pin "11") (pinfunction "VS_11") (pintype "power_in"))
    )
    (net (code "74") (name "unconnected-(J1-NC-Pad7)") (class "Default")
      (node (ref "J1") (pin "7") (pinfunction "NC_7") (pintype "no_connect"))
    )
    (net (code "75") (name "unconnected-(J2-PWR-PadVIN0)") (class "Default")
      (node (ref "J2") (pin "VIN0") (pinfunction "PWR_VIN0") (pintype "bidirectional"))
    )
    (net (code "76") (name "unconnected-(JP1-Pad9)") (class "Default")
      (node (ref "JP1") (pin "9") (pinfunction "9_9") (pintype "passive"))
    )
    (net (code "77") (name "unconnected-(JP1-Pad12)") (class "Default")
      (node (ref "JP1") (pin "12") (pinfunction "12_12") (pintype "passive"))
    )
    (net (code "78") (name "unconnected-(JP1-Pad15)") (class "Default")
      (node (ref "JP1") (pin "15") (pinfunction "15_15") (pintype "passive"))
    )
    (net (code "79") (name "unconnected-(JP1-Pad16)") (class "Default")
      (node (ref "JP1") (pin "16") (pinfunction "16_16") (pintype "passive"))
    )
    (net (code "80") (name "unconnected-(U1-NC-Pad19)") (class "Default")
      (node (ref "U1") (pin "19") (pinfunction "NC_19") (pintype "no_connect"))
    )
    (net (code "81") (name "unconnected-(U1-NC-Pad20)") (class "Default")
      (node (ref "U1") (pin "20") (pinfunction "NC_20") (pintype "no_connect"))
    )
    (net (code "82") (name "unconnected-(U1-PIO0_1{slash}CLKOUT{slash}CT32B0_MAT2-Pad4)") (class "Default")
      (node (ref "U1") (pin "4") (pinfunction "PIO0_1/CLKOUT/CT32B0_MAT2_4") (pintype "bidirectional"))
    )
    (net (code "83") (name "unconnected-(U1-PIO0_23{slash}AD7-Pad42)") (class "Default")
      (node (ref "U1") (pin "42") (pinfunction "PIO0_23/AD7_42") (pintype "bidirectional"))
    )
    (net (code "84") (name "unconnected-(U1-PIO1_14{slash}~{DSR}{slash}CT16B0_MAT1{slash}RXD-Pad37)") (class "Default")
      (node (ref "U1") (pin "37") (pinfunction "PIO1_14/~{DSR}/CT16B0_MAT1/RXD_37") (pintype "bidirectional"))
    )
    (net (code "85") (name "unconnected-(U1-PIO1_15{slash}~{DCD}{slash}CT16B0_MAT2{slash}SCK1-Pad43)") (class "Default")
      (node (ref "U1") (pin "43") (pinfunction "PIO1_15/~{DCD}/CT16B0_MAT2/SCK1_43") (pintype "bidirectional"))
    )
    (net (code "86") (name "unconnected-(U1-PIO1_19{slash}~{DTR}{slash}SSEL1-Pad2)") (class "Default")
      (node (ref "U1") (pin "2") (pinfunction "PIO1_19/~{DTR}/SSEL1_2") (pintype "bidirectional"))
    )
    (net (code "87") (name "unconnected-(U1-~{TRST}{slash}PIO0_14{slash}AD3{slash}CT32B1_MAT1-Pad35)") (class "Default")
      (node (ref "U1") (pin "35") (pinfunction "~{TRST}/PIO0_14/AD3/CT32B1_MAT1_35") (pintype "bidirectional"))
    )
    (net (code "88") (name "unconnected-(U2-NR-Pad5)") (class "Default")
      (node (ref "U2") (pin "5") (pinfunction "NR_5") (pintype "input"))
    )
    (net (code "89") (name "unconnected-(U2-~{ERR}-Pad3)") (class "Default")
      (node (ref "U2") (pin "3") (pinfunction "~{ERR}_3") (pintype "output"))
    )
  )
)
